# WatchMe-BASIC-BOTTOM.net
KiCad netlist of a schematic drawn in EAGLE
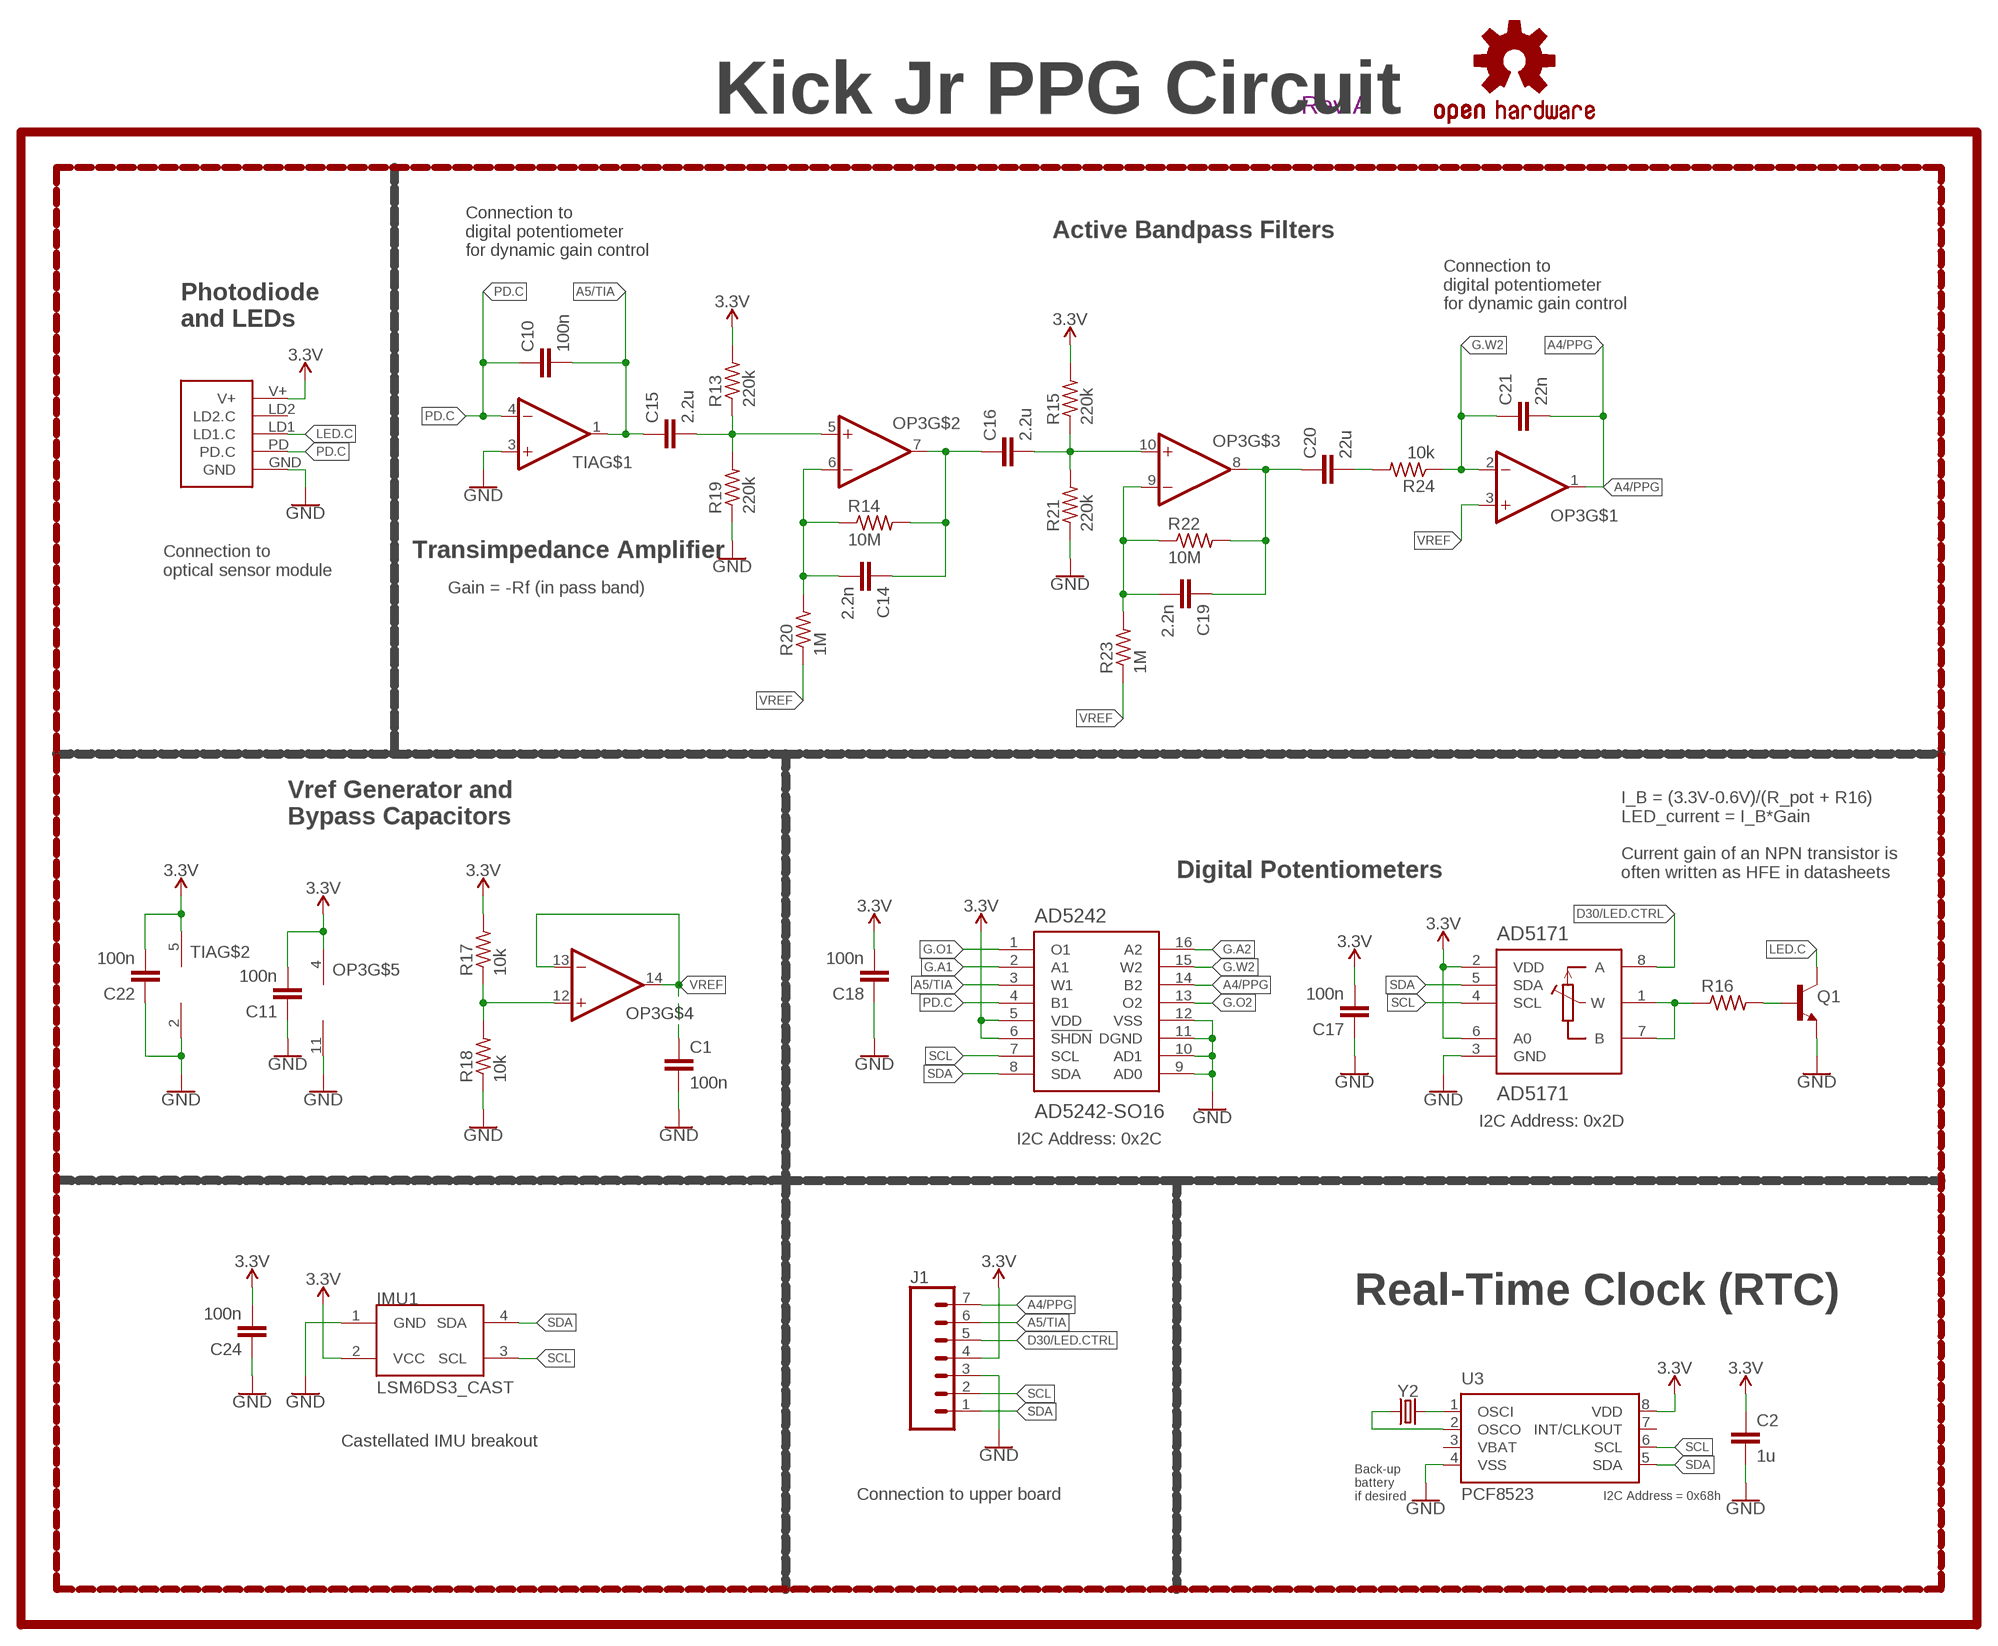
[diagram p0: schematic, sheet 1]

(export (version "E")
  (design (tool "Eeschema 10.0.6"))
  (components
    (comp (ref "AD5171")
      (value "AD5171")
      (footprint "eagle-import:SOT-23-8")
      (libsource (lib "eagle-import") (part "AD5171"))
    )
    (comp (ref "AD5242")
      (value "AD5242-SO16")
      (footprint "eagle-import:SO16")
      (libsource (lib "eagle-import") (part "AD5242-SO16"))
    )
    (comp (ref "C1")
      (value "100n")
      (footprint "eagle-import:C0603")
      (libsource (lib "eagle-import") (part "CAPACITOR0603"))
    )
    (comp (ref "C2")
      (value "1u")
      (footprint "eagle-import:C0603")
      (libsource (lib "eagle-import") (part "CAPACITOR0603"))
    )
    (comp (ref "C10")
      (value "100n")
      (footprint "eagle-import:C0603")
      (libsource (lib "eagle-import") (part "CAPACITOR0603"))
    )
    (comp (ref "C11")
      (value "100n")
      (footprint "eagle-import:C0603")
      (libsource (lib "eagle-import") (part "CAPACITOR0603"))
    )
    (comp (ref "C14")
      (value "2.2n")
      (footprint "eagle-import:C0603")
      (libsource (lib "eagle-import") (part "CAPACITOR0603"))
    )
    (comp (ref "C15")
      (value "2.2u")
      (footprint "eagle-import:C0603")
      (libsource (lib "eagle-import") (part "CAPACITOR0603"))
    )
    (comp (ref "C16")
      (value "2.2u")
      (footprint "eagle-import:C0603")
      (libsource (lib "eagle-import") (part "CAPACITOR0603"))
    )
    (comp (ref "C17")
      (value "100n")
      (footprint "eagle-import:C0603")
      (libsource (lib "eagle-import") (part "CAPACITOR0603"))
    )
    (comp (ref "C18")
      (value "100n")
      (footprint "eagle-import:C0603")
      (libsource (lib "eagle-import") (part "CAPACITOR0603"))
    )
    (comp (ref "C19")
      (value "2.2n")
      (footprint "eagle-import:C0603")
      (libsource (lib "eagle-import") (part "CAPACITOR0603"))
    )
    (comp (ref "C20")
      (value "22u")
      (footprint "eagle-import:C0603")
      (libsource (lib "eagle-import") (part "CAPACITOR0603"))
    )
    (comp (ref "C21")
      (value "22n")
      (footprint "eagle-import:C0603")
      (libsource (lib "eagle-import") (part "CAPACITOR0603"))
    )
    (comp (ref "C22")
      (value "100n")
      (footprint "eagle-import:C0603")
      (libsource (lib "eagle-import") (part "CAPACITOR0603"))
    )
    (comp (ref "C24")
      (value "100n")
      (footprint "eagle-import:C0603")
      (libsource (lib "eagle-import") (part "CAPACITOR0603"))
    )
    (comp (ref "IMU1")
      (value "LSM6DS3_CAST")
      (footprint "eagle-import:LSM6DS3_CAST")
      (libsource (lib "eagle-import") (part "LSM6DS3_CAST"))
    )
    (comp (ref "J1")
      (value "CONN_07-1.27MM")
      (footprint "eagle-import:1X07_1.27MM")
      (libsource (lib "eagle-import") (part "CONN_07-1.27MM"))
    )
    (comp (ref "LOGO1")
      (value "REVISION.A")
      (footprint "eagle-import:REV.A")
      (libsource (lib "eagle-import") (part "REVISION.A"))
    )
    (comp (ref "LOGO2")
      (value "OSHW-LOGOS")
      (footprint "eagle-import:OSHW-LOGO-S")
      (libsource (lib "eagle-import") (part "OSHW-LOGOS"))
    )
    (comp (ref "OP3")
      (value "OP-QUAD-SO14")
      (footprint "eagle-import:SO14")
      (libsource (lib "eagle-import") (part "OP-QUAD-SO14"))
    )
    (comp (ref "Q1")
      (value "NPN-GENERIC")
      (footprint "eagle-import:SOT23-3")
      (libsource (lib "eagle-import") (part "NPN-GENERIC"))
    )
    (comp (ref "R13")
      (value "220k")
      (footprint "eagle-import:R0603")
      (libsource (lib "eagle-import") (part "RESISTOR0603"))
    )
    (comp (ref "R14")
      (value "10M")
      (footprint "eagle-import:R0603")
      (libsource (lib "eagle-import") (part "RESISTOR0603"))
    )
    (comp (ref "R15")
      (value "220k")
      (footprint "eagle-import:R0603")
      (libsource (lib "eagle-import") (part "RESISTOR0603"))
    )
    (comp (ref "R16")
      (value "RESISTOR0603")
      (footprint "eagle-import:R0603")
      (libsource (lib "eagle-import") (part "RESISTOR0603"))
    )
    (comp (ref "R17")
      (value "10k")
      (footprint "eagle-import:R0402")
      (libsource (lib "eagle-import") (part "RESISTOR0402"))
    )
    (comp (ref "R18")
      (value "10k")
      (footprint "eagle-import:R0402")
      (libsource (lib "eagle-import") (part "RESISTOR0402"))
    )
    (comp (ref "R19")
      (value "220k")
      (footprint "eagle-import:R0603")
      (libsource (lib "eagle-import") (part "RESISTOR0603"))
    )
    (comp (ref "R20")
      (value "1M")
      (footprint "eagle-import:R0603")
      (libsource (lib "eagle-import") (part "RESISTOR0603"))
    )
    (comp (ref "R21")
      (value "220k")
      (footprint "eagle-import:R0603")
      (libsource (lib "eagle-import") (part "RESISTOR0603"))
    )
    (comp (ref "R22")
      (value "10M")
      (footprint "eagle-import:R0603")
      (libsource (lib "eagle-import") (part "RESISTOR0603"))
    )
    (comp (ref "R23")
      (value "1M")
      (footprint "eagle-import:R0603")
      (libsource (lib "eagle-import") (part "RESISTOR0603"))
    )
    (comp (ref "R24")
      (value "10k")
      (footprint "eagle-import:R0603")
      (libsource (lib "eagle-import") (part "RESISTOR0603"))
    )
    (comp (ref "TIA")
      (value "OP-SINGLEOT")
      (footprint "eagle-import:SOT23-5")
      (libsource (lib "eagle-import") (part "OP-SINGLEOT"))
    )
    (comp (ref "U$3")
      (value "PPG.MODULE.2")
      (footprint "eagle-import:PPG.MODULE.2")
      (libsource (lib "eagle-import") (part "PPG.MODULE.2"))
    )
    (comp (ref "U3")
      (value "PCF8523")
      (footprint "eagle-import:SO8")
      (fields
        (field (name "DIGIKEY") "568-5306-1-ND")
        (field (name "I2C_ADDRESS") "0x68h")
        (field (name "MFN") "PCF8523T/1,118")
        (field (name "MFN_MANUFACTURER") "NXP USA Inc.")
      )
      (libsource (lib "eagle-import") (part "PCF8523"))
    )
    (comp (ref "Y2")
      (value "32.7680kHz")
      (footprint "eagle-import:2-SMD.NOLEAD.2.0MMTO1.2MM")
      (fields (field (name "FREQ") "32.7680KHZ"))
      (libsource (lib "eagle-import") (part "CRYSTALECS-.327-12.5-12-C-TR"))
    )
  )
  (nets
    (net (code "1") (name "/VBAT") (class "Default")
      (node (ref "U3") (pin "3") (pinfunction "VBAT_3") (pintype "power_in"))
    )
    (net (code "2") (name "3.3V") (class "Default")
      (node (ref "AD5171") (pin "2") (pinfunction "VDD_2") (pintype "bidirectional"))
      (node (ref "AD5171") (pin "6") (pinfunction "A0_6") (pintype "bidirectional"))
      (node (ref "AD5242") (pin "5") (pinfunction "VDD_5") (pintype "bidirectional"))
      (node (ref "AD5242") (pin "6") (pinfunction "~{SHDN}_6") (pintype "bidirectional"))
      (node (ref "C11") (pin "2") (pinfunction "2_2") (pintype "passive"))
      (node (ref "C17") (pin "2") (pinfunction "2_2") (pintype "passive"))
      (node (ref "C18") (pin "2") (pinfunction "2_2") (pintype "passive"))
      (node (ref "C2") (pin "1") (pinfunction "1_1") (pintype "passive"))
      (node (ref "C22") (pin "2") (pinfunction "2_2") (pintype "passive"))
      (node (ref "C24") (pin "2") (pinfunction "2_2") (pintype "passive"))
      (node (ref "IMU1") (pin "2") (pinfunction "VCC_2") (pintype "bidirectional"))
      (node (ref "J1") (pin "4") (pinfunction "4_4") (pintype "passive"))
      (node (ref "OP3") (pin "4") (pinfunction "V+_4") (pintype "power_in"))
      (node (ref "R13") (pin "2") (pinfunction "2_2") (pintype "passive"))
      (node (ref "R15") (pin "2") (pinfunction "2_2") (pintype "passive"))
      (node (ref "R17") (pin "2") (pinfunction "2_2") (pintype "passive"))
      (node (ref "TIA") (pin "5") (pinfunction "V+_5") (pintype "power_in"))
      (node (ref "U$3") (pin "V+") (pinfunction "V+_V+") (pintype "bidirectional"))
      (node (ref "U3") (pin "8") (pinfunction "VDD_8") (pintype "power_in"))
    )
    (net (code "3") (name "A4{slash}PPG") (class "Default")
      (node (ref "AD5242") (pin "14") (pinfunction "B2_14") (pintype "bidirectional"))
      (node (ref "C21") (pin "2") (pinfunction "2_2") (pintype "passive"))
      (node (ref "J1") (pin "7") (pinfunction "7_7") (pintype "passive"))
      (node (ref "OP3") (pin "1") (pinfunction "OUT_1") (pintype "output"))
    )
    (net (code "4") (name "A5{slash}TIA") (class "Default")
      (node (ref "AD5242") (pin "3") (pinfunction "W1_3") (pintype "bidirectional"))
      (node (ref "C10") (pin "2") (pinfunction "2_2") (pintype "passive"))
      (node (ref "C15") (pin "1") (pinfunction "1_1") (pintype "passive"))
      (node (ref "J1") (pin "6") (pinfunction "6_6") (pintype "passive"))
      (node (ref "TIA") (pin "1") (pinfunction "OUT_1") (pintype "output"))
    )
    (net (code "5") (name "D30{slash}LED.CTRL") (class "Default")
      (node (ref "AD5171") (pin "8") (pinfunction "A_8") (pintype "bidirectional"))
      (node (ref "J1") (pin "5") (pinfunction "5_5") (pintype "passive"))
    )
    (net (code "6") (name "G.A1") (class "Default")
      (node (ref "AD5242") (pin "2") (pinfunction "A1_2") (pintype "bidirectional"))
    )
    (net (code "7") (name "G.A2") (class "Default")
      (node (ref "AD5242") (pin "16") (pinfunction "A2_16") (pintype "bidirectional"))
    )
    (net (code "8") (name "G.O1") (class "Default")
      (node (ref "AD5242") (pin "1") (pinfunction "O1_1") (pintype "bidirectional"))
    )
    (net (code "9") (name "G.O2") (class "Default")
      (node (ref "AD5242") (pin "13") (pinfunction "O2_13") (pintype "bidirectional"))
    )
    (net (code "10") (name "G.W2") (class "Default")
      (node (ref "AD5242") (pin "15") (pinfunction "W2_15") (pintype "bidirectional"))
      (node (ref "C21") (pin "1") (pinfunction "1_1") (pintype "passive"))
      (node (ref "OP3") (pin "2") (pinfunction "-IN_2") (pintype "input"))
      (node (ref "R24") (pin "1") (pinfunction "1_1") (pintype "passive"))
    )
    (net (code "11") (name "GND") (class "Default")
      (node (ref "AD5171") (pin "3") (pinfunction "GND_3") (pintype "bidirectional"))
      (node (ref "AD5242") (pin "10") (pinfunction "AD1_10") (pintype "bidirectional"))
      (node (ref "AD5242") (pin "11") (pinfunction "DGND_11") (pintype "bidirectional"))
      (node (ref "AD5242") (pin "12") (pinfunction "VSS_12") (pintype "bidirectional"))
      (node (ref "AD5242") (pin "9") (pinfunction "AD0_9") (pintype "bidirectional"))
      (node (ref "C1") (pin "2") (pinfunction "2_2") (pintype "passive"))
      (node (ref "C11") (pin "1") (pinfunction "1_1") (pintype "passive"))
      (node (ref "C17") (pin "1") (pinfunction "1_1") (pintype "passive"))
      (node (ref "C18") (pin "1") (pinfunction "1_1") (pintype "passive"))
      (node (ref "C2") (pin "2") (pinfunction "2_2") (pintype "passive"))
      (node (ref "C22") (pin "1") (pinfunction "1_1") (pintype "passive"))
      (node (ref "C24") (pin "1") (pinfunction "1_1") (pintype "passive"))
      (node (ref "IMU1") (pin "1") (pinfunction "GND_1") (pintype "bidirectional"))
      (node (ref "J1") (pin "3") (pinfunction "3_3") (pintype "passive"))
      (node (ref "OP3") (pin "11") (pinfunction "V-_11") (pintype "power_in"))
      (node (ref "Q1") (pin "2") (pinfunction "E_2") (pintype "passive"))
      (node (ref "R18") (pin "1") (pinfunction "1_1") (pintype "passive"))
      (node (ref "R19") (pin "1") (pinfunction "1_1") (pintype "passive"))
      (node (ref "R21") (pin "1") (pinfunction "1_1") (pintype "passive"))
      (node (ref "TIA") (pin "2") (pinfunction "V-_2") (pintype "power_in"))
      (node (ref "TIA") (pin "3") (pinfunction "+IN_3") (pintype "input"))
      (node (ref "U$3") (pin "GND") (pinfunction "GND_GND") (pintype "bidirectional"))
      (node (ref "U3") (pin "4") (pinfunction "VSS_4") (pintype "power_in"))
    )
    (net (code "12") (name "LED.C") (class "Default")
      (node (ref "Q1") (pin "3") (pinfunction "C_3") (pintype "passive"))
      (node (ref "U$3") (pin "LD1") (pinfunction "LD1.C_LD1") (pintype "bidirectional"))
    )
    (net (code "13") (name "Net-(AD5171-B)") (class "Default")
      (node (ref "AD5171") (pin "1") (pinfunction "W_1") (pintype "bidirectional"))
      (node (ref "AD5171") (pin "7") (pinfunction "B_7") (pintype "bidirectional"))
      (node (ref "R16") (pin "1") (pinfunction "1_1") (pintype "passive"))
    )
    (net (code "14") (name "Net-(C20-Pad2)") (class "Default")
      (node (ref "C20") (pin "2") (pinfunction "2_2") (pintype "passive"))
      (node (ref "R24") (pin "2") (pinfunction "2_2") (pintype "passive"))
    )
    (net (code "15") (name "Net-(OP3B-+IN)") (class "Default")
      (node (ref "C15") (pin "2") (pinfunction "2_2") (pintype "passive"))
      (node (ref "OP3") (pin "5") (pinfunction "+IN_5") (pintype "input"))
      (node (ref "R13") (pin "1") (pinfunction "1_1") (pintype "passive"))
      (node (ref "R19") (pin "2") (pinfunction "2_2") (pintype "passive"))
    )
    (net (code "16") (name "Net-(OP3B--IN)") (class "Default")
      (node (ref "C14") (pin "2") (pinfunction "2_2") (pintype "passive"))
      (node (ref "OP3") (pin "6") (pinfunction "-IN_6") (pintype "input"))
      (node (ref "R14") (pin "1") (pinfunction "1_1") (pintype "passive"))
      (node (ref "R20") (pin "2") (pinfunction "2_2") (pintype "passive"))
    )
    (net (code "17") (name "Net-(OP3B-OUT)") (class "Default")
      (node (ref "C14") (pin "1") (pinfunction "1_1") (pintype "passive"))
      (node (ref "C16") (pin "1") (pinfunction "1_1") (pintype "passive"))
      (node (ref "OP3") (pin "7") (pinfunction "OUT_7") (pintype "output"))
      (node (ref "R14") (pin "2") (pinfunction "2_2") (pintype "passive"))
    )
    (net (code "18") (name "Net-(OP3C-+IN)") (class "Default")
      (node (ref "C16") (pin "2") (pinfunction "2_2") (pintype "passive"))
      (node (ref "OP3") (pin "10") (pinfunction "+IN_10") (pintype "input"))
      (node (ref "R15") (pin "1") (pinfunction "1_1") (pintype "passive"))
      (node (ref "R21") (pin "2") (pinfunction "2_2") (pintype "passive"))
    )
    (net (code "19") (name "Net-(OP3C--IN)") (class "Default")
      (node (ref "C19") (pin "2") (pinfunction "2_2") (pintype "passive"))
      (node (ref "OP3") (pin "9") (pinfunction "-IN_9") (pintype "input"))
      (node (ref "R22") (pin "1") (pinfunction "1_1") (pintype "passive"))
      (node (ref "R23") (pin "2") (pinfunction "2_2") (pintype "passive"))
    )
    (net (code "20") (name "Net-(OP3C-OUT)") (class "Default")
      (node (ref "C19") (pin "1") (pinfunction "1_1") (pintype "passive"))
      (node (ref "C20") (pin "1") (pinfunction "1_1") (pintype "passive"))
      (node (ref "OP3") (pin "8") (pinfunction "OUT_8") (pintype "output"))
      (node (ref "R22") (pin "2") (pinfunction "2_2") (pintype "passive"))
    )
    (net (code "21") (name "Net-(OP3D-+IN)") (class "Default")
      (node (ref "OP3") (pin "12") (pinfunction "+IN_12") (pintype "input"))
      (node (ref "R17") (pin "1") (pinfunction "1_1") (pintype "passive"))
      (node (ref "R18") (pin "2") (pinfunction "2_2") (pintype "passive"))
    )
    (net (code "22") (name "Net-(Q1-B)") (class "Default")
      (node (ref "Q1") (pin "1") (pinfunction "B_1") (pintype "passive"))
      (node (ref "R16") (pin "2") (pinfunction "2_2") (pintype "passive"))
    )
    (net (code "23") (name "Net-(U3-OSCI)") (class "Default")
      (node (ref "U3") (pin "1") (pinfunction "OSCI_1") (pintype "bidirectional"))
      (node (ref "Y2") (pin "P$2") (pinfunction "2_P$2") (pintype "passive"))
    )
    (net (code "24") (name "Net-(U3-OSCO)") (class "Default")
      (node (ref "U3") (pin "2") (pinfunction "OSCO_2") (pintype "bidirectional"))
      (node (ref "Y2") (pin "P$1") (pinfunction "1_P$1") (pintype "passive"))
    )
    (net (code "25") (name "PD.C") (class "Default")
      (node (ref "AD5242") (pin "4") (pinfunction "B1_4") (pintype "bidirectional"))
      (node (ref "C10") (pin "1") (pinfunction "1_1") (pintype "passive"))
      (node (ref "TIA") (pin "4") (pinfunction "-IN_4") (pintype "input"))
      (node (ref "U$3") (pin "PD") (pinfunction "PD.C_PD") (pintype "bidirectional"))
    )
    (net (code "26") (name "SCL") (class "Default")
      (node (ref "AD5171") (pin "4") (pinfunction "SCL_4") (pintype "bidirectional"))
      (node (ref "AD5242") (pin "7") (pinfunction "SCL_7") (pintype "bidirectional"))
      (node (ref "IMU1") (pin "3") (pinfunction "SCL_3") (pintype "bidirectional"))
      (node (ref "J1") (pin "2") (pinfunction "2_2") (pintype "passive"))
      (node (ref "U3") (pin "6") (pinfunction "SCL_6") (pintype "bidirectional"))
    )
    (net (code "27") (name "SDA") (class "Default")
      (node (ref "AD5171") (pin "5") (pinfunction "SDA_5") (pintype "bidirectional"))
      (node (ref "AD5242") (pin "8") (pinfunction "SDA_8") (pintype "bidirectional"))
      (node (ref "IMU1") (pin "4") (pinfunction "SDA_4") (pintype "bidirectional"))
      (node (ref "J1") (pin "1") (pinfunction "1_1") (pintype "passive"))
      (node (ref "U3") (pin "5") (pinfunction "SDA_5") (pintype "bidirectional"))
    )
    (net (code "28") (name "VREF") (class "Default")
      (node (ref "C1") (pin "1") (pinfunction "1_1") (pintype "passive"))
      (node (ref "OP3") (pin "13") (pinfunction "-IN_13") (pintype "input"))
      (node (ref "OP3") (pin "14") (pinfunction "OUT_14") (pintype "output"))
      (node (ref "OP3") (pin "3") (pinfunction "+IN_3") (pintype "input"))
      (node (ref "R20") (pin "1") (pinfunction "1_1") (pintype "passive"))
      (node (ref "R23") (pin "1") (pinfunction "1_1") (pintype "passive"))
    )
    (net (code "29") (name "unconnected-(U$3-LD2.C-PadLD2)") (class "Default")
      (node (ref "U$3") (pin "LD2") (pinfunction "LD2.C_LD2") (pintype "bidirectional"))
    )
    (net (code "30") (name "unconnected-(U3-INT{slash}CLKOUT-Pad7)") (class "Default")
      (node (ref "U3") (pin "7") (pinfunction "INT/CLKOUT_7") (pintype "bidirectional"))
    )
  )
)
